# Sensors.net
KiCad netlist of a schematic drawn in Altium Designer
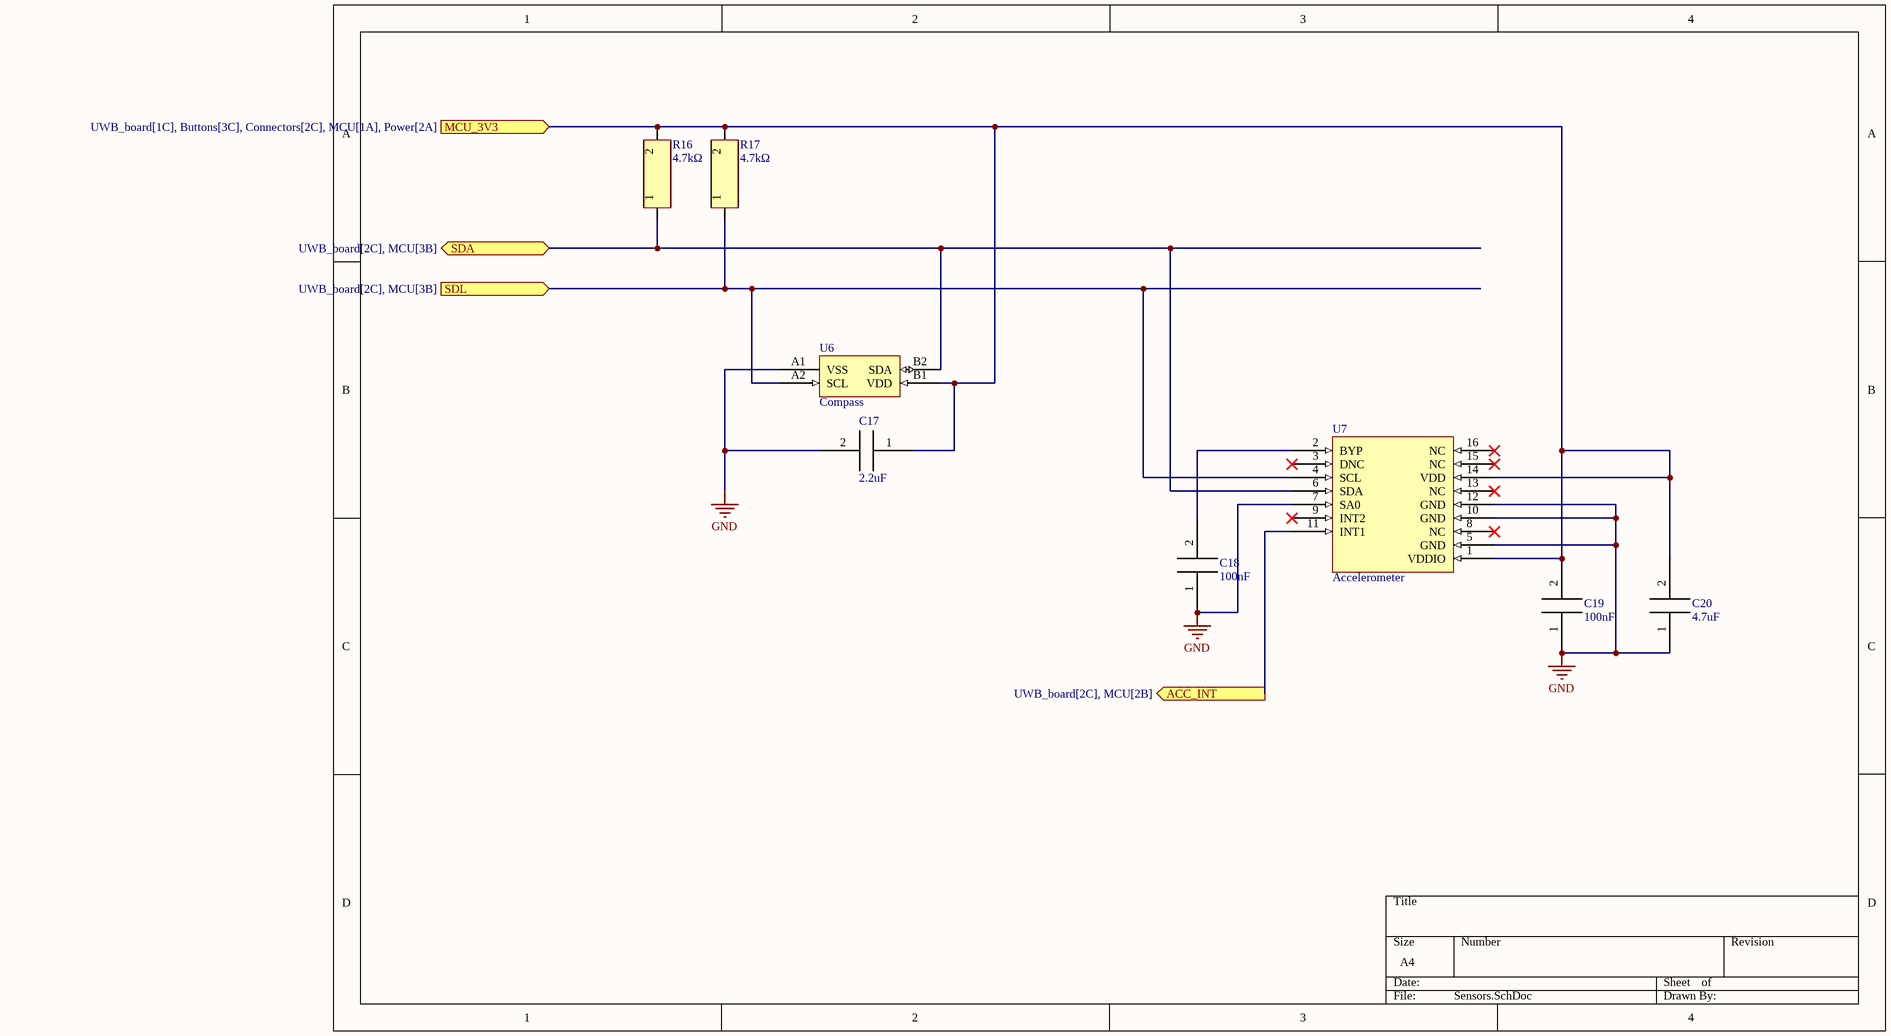
[diagram p0: Sensors.SchDoc]

(export (version "E")
  (design (tool "Eeschema 10.0.6"))
  (components
    (comp (ref "C17")
      (value "2.2uF")
      (footprint "0603_cap")
      (description "2.2uF 16V X5R ±10% 0603 Multilayer Ceramic Capacitors MLCC - SMD/SMT ROHS")
      (fields (field (name "LCSC PART #") "C23630"))
      (libsource (lib "Schlib1") (part "CL10A225KO8NNNC"))
    )
    (comp (ref "C18")
      (value "100nF")
      (footprint "0603_cap")
      (description "100nF 50V X7R ±10% 0603 Multilayer Ceramic Capacitors MLCC - SMD/SMT ROHS")
      (fields (field (name "LCSC PART #") "C14663"))
      (libsource (lib "Schlib1") (part "CC0603KRX7R9BB104"))
    )
    (comp (ref "C19")
      (value "100nF")
      (footprint "0603_cap")
      (description "100nF 50V X7R ±10% 0603 Multilayer Ceramic Capacitors MLCC - SMD/SMT ROHS")
      (fields (field (name "LCSC PART #") "C14663"))
      (libsource (lib "Schlib1") (part "CC0603KRX7R9BB104"))
    )
    (comp (ref "C20")
      (value "4.7uF")
      (footprint "0603_cap")
      (description "4.7uF 50V X7R ±10% 0603 Multilayer Ceramic Capacitors MLCC - SMD/SMT ROHS")
      (fields (field (name "LCSC PART #") "C19666"))
      (libsource (lib "Schlib1") (part "CL10A475KO8NNNC"))
    )
    (comp (ref "R16")
      (value "4.7kΩ")
      (footprint "0603_res")
      (fields (field (name "LCSC PART #") "C23162") (field (name "Comment") "4.7k"))
      (libsource (lib "Schlib1") (part "0603WAF4701T5E"))
    )
    (comp (ref "R17")
      (value "4.7kΩ")
      (footprint "0603_res")
      (fields (field (name "LCSC PART #") "C23162") (field (name "Comment") "4.7k"))
      (libsource (lib "Schlib1") (part "0603WAF4701T5E"))
    )
    (comp (ref "U6")
      (value "Compass")
      (footprint "BGA4C40P2X2_79X79X58")
      (description "-40℃~+85℃ 16bit 2.5V~3.6V 6uA I2C ±3.2mT ±3.2mT WLCSP-4(0.8x0.8) 3D Magnetic Sensors ROHS")
      (fields (field (name "LCSC PART #") "C5439871"))
      (libsource (lib "Schlib1") (part "QMC6309"))
    )
    (comp (ref "U7")
      (value "Accelerometer")
      (footprint "QFN50P300X300X100-16N")
      (description "-40℃~+85℃ 1.8uA 1.95V~3.6V 14bit Accelerometer I2C X,Y,Z ±8g QFN-16(3x3) Accelerometers ROHS")
      (fields (field (name "LCSC PART #") "C118083"))
      (libsource (lib "Schlib1") (part "MMA8451QR1"))
    )
  )
  (nets
    (net (code "1") (name "/ACC_INT") (class "Default")
      (node (ref "U7") (pin "11") (pinfunction "INT1_11") (pintype "input"))
    )
    (net (code "2") (name "/MCU_3V3") (class "Default")
      (node (ref "C17") (pin "1") (pintype "passive"))
      (node (ref "C19") (pin "2") (pinfunction "3_2") (pintype "passive"))
      (node (ref "C20") (pin "2") (pinfunction "3_2") (pintype "passive"))
      (node (ref "R16") (pin "2") (pinfunction "3_2") (pintype "passive"))
      (node (ref "R17") (pin "2") (pinfunction "3_2") (pintype "passive"))
      (node (ref "U6") (pin "B1") (pinfunction "VDD_B1") (pintype "input"))
      (node (ref "U7") (pin "1") (pinfunction "VDDIO_1") (pintype "input"))
      (node (ref "U7") (pin "14") (pinfunction "VDD_14") (pintype "input"))
    )
    (net (code "3") (name "/SDA") (class "Default")
      (node (ref "R16") (pin "1") (pinfunction "1_1") (pintype "passive"))
      (node (ref "U6") (pin "B2") (pinfunction "SDA_B2") (pintype "bidirectional"))
      (node (ref "U7") (pin "6") (pinfunction "SDA_6") (pintype "input"))
    )
    (net (code "4") (name "/SDL") (class "Default")
      (node (ref "R17") (pin "1") (pinfunction "1_1") (pintype "passive"))
      (node (ref "U6") (pin "A2") (pinfunction "SCL_A2") (pintype "input"))
      (node (ref "U7") (pin "4") (pinfunction "SCL_4") (pintype "input"))
    )
    (net (code "5") (name "GND") (class "Default")
      (node (ref "C17") (pin "2") (pinfunction "3_2") (pintype "passive"))
      (node (ref "C18") (pin "1") (pintype "passive"))
      (node (ref "C19") (pin "1") (pintype "passive"))
      (node (ref "C20") (pin "1") (pintype "passive"))
      (node (ref "U6") (pin "A1") (pinfunction "VSS_A1") (pintype "power_in"))
      (node (ref "U7") (pin "10") (pinfunction "GND_10") (pintype "input"))
      (node (ref "U7") (pin "12") (pinfunction "GND_12") (pintype "input"))
      (node (ref "U7") (pin "5") (pinfunction "GND_5") (pintype "input"))
      (node (ref "U7") (pin "7") (pinfunction "SA0_7") (pintype "input"))
    )
    (net (code "6") (name "Net-(C18-3)") (class "Default")
      (node (ref "C18") (pin "2") (pinfunction "3_2") (pintype "passive"))
      (node (ref "U7") (pin "2") (pinfunction "BYP_2") (pintype "input"))
    )
    (net (code "7") (name "unconnected-(U7-DNC-Pad3)") (class "Default")
      (node (ref "U7") (pin "3") (pinfunction "DNC_3") (pintype "input+no_connect"))
    )
    (net (code "8") (name "unconnected-(U7-INT2-Pad9)") (class "Default")
      (node (ref "U7") (pin "9") (pinfunction "INT2_9") (pintype "input+no_connect"))
    )
    (net (code "9") (name "unconnected-(U7-NC-Pad8)") (class "Default")
      (node (ref "U7") (pin "8") (pinfunction "NC_8") (pintype "input+no_connect"))
    )
    (net (code "10") (name "unconnected-(U7-NC-Pad13)") (class "Default")
      (node (ref "U7") (pin "13") (pinfunction "NC_13") (pintype "input+no_connect"))
    )
    (net (code "11") (name "unconnected-(U7-NC-Pad15)") (class "Default")
      (node (ref "U7") (pin "15") (pinfunction "NC_15") (pintype "input+no_connect"))
    )
    (net (code "12") (name "unconnected-(U7-NC-Pad16)") (class "Default")
      (node (ref "U7") (pin "16") (pinfunction "NC_16") (pintype "input+no_connect"))
    )
  )
)
